# FPGA_Peripherals_Control.net
KiCad netlist of a schematic drawn in Altium Designer
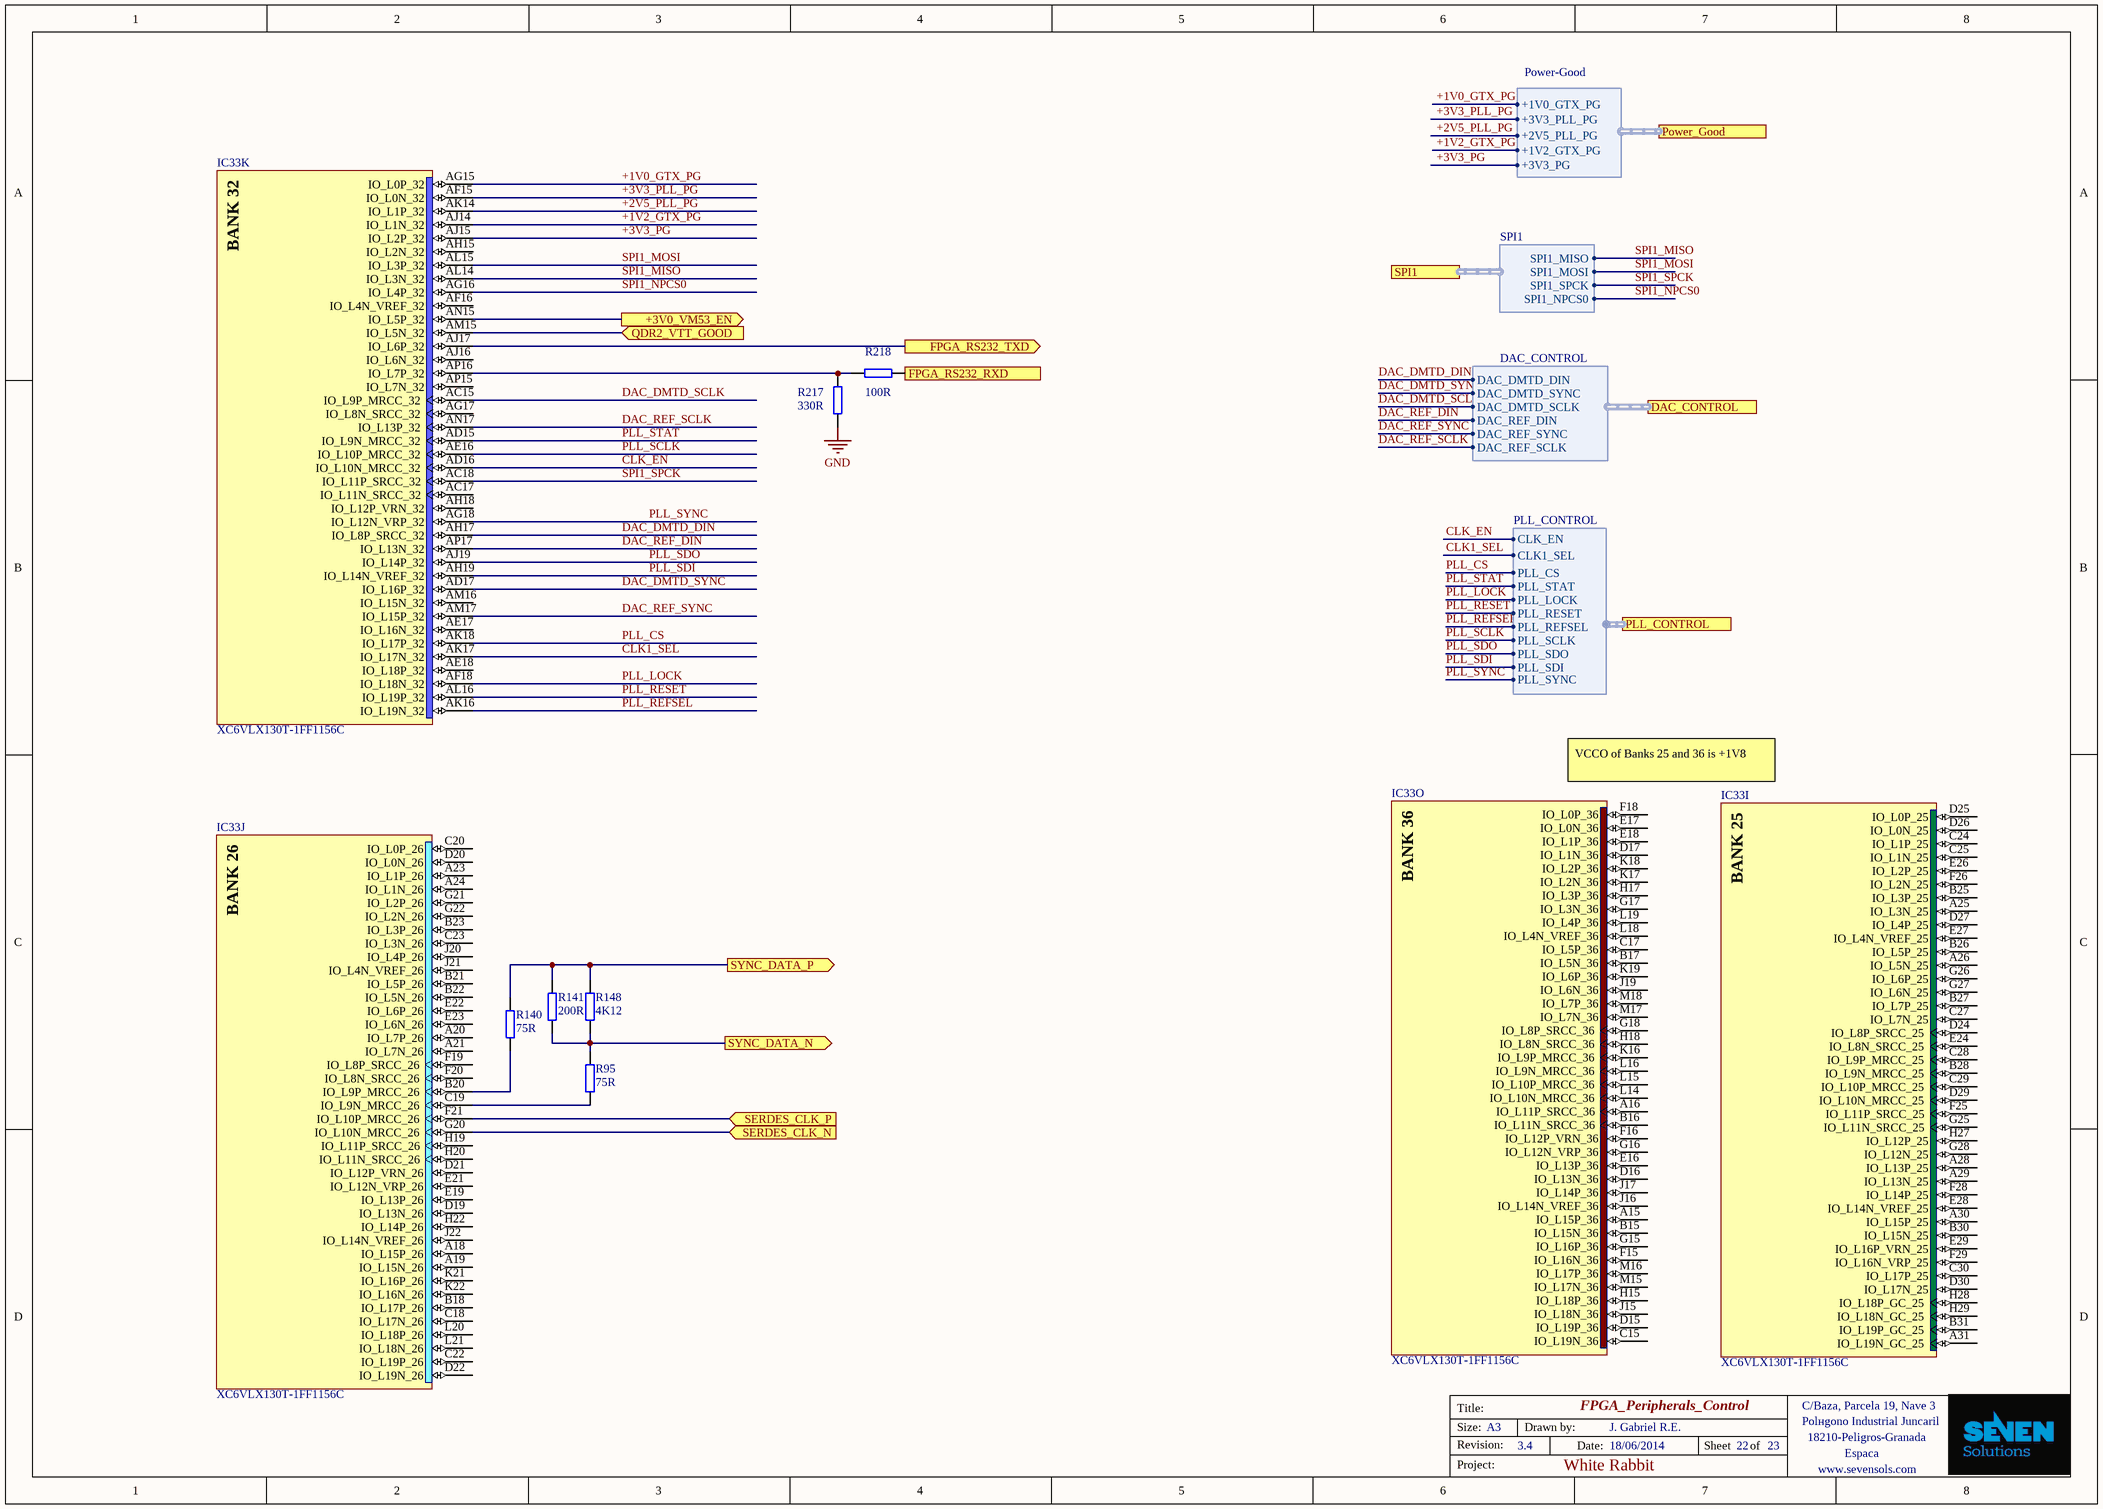
[diagram p0: FPGA_Peripherals_Control.SchDoc]

(export (version "E")
  (design (tool "Eeschema 10.0.6"))
  (components
    (comp (ref "IC33")
      (value "XC6VLX130T-1FF1156C")
      (footprint "FF1156")
      (fields (field (name "PUBLISHER") "Altium Limited"))
      (libsource (lib "Xilinx Virtex-6") (part "XC6VLX130T-1FF1156C"))
    )
    (comp (ref "R95")
      (value "75R")
      (footprint "0402")
      (description "SMD Resistor")
      (fields (field (name "TOLERANCE") "±1%"))
      (libsource (lib "wr_switch") (part "RES_SMD"))
    )
    (comp (ref "R140")
      (value "75R")
      (footprint "0402")
      (description "SMD Resistor")
      (fields (field (name "TOLERANCE") "±1%"))
      (libsource (lib "wr_switch") (part "RES_SMD"))
    )
    (comp (ref "R141")
      (value "200R")
      (footprint "0402")
      (description "SMD Resistor")
      (fields (field (name "TOLERANCE") "±1%"))
      (libsource (lib "wr_switch") (part "RES_SMD"))
    )
    (comp (ref "R148")
      (value "4K12")
      (footprint "0402")
      (description "SMD Resistor")
      (fields (field (name "TOLERANCE") "±1%"))
      (libsource (lib "wr_switch") (part "RES_SMD"))
    )
    (comp (ref "R217")
      (value "330R")
      (footprint "0402")
      (description "SMD Resistor")
      (fields (field (name "TOLERANCE") "±1%"))
      (libsource (lib "wr_switch") (part "RES_SMD"))
    )
    (comp (ref "R218")
      (value "100R")
      (footprint "0402")
      (description "SMD Resistor")
      (fields (field (name "TOLERANCE") "±1%"))
      (libsource (lib "wr_switch") (part "RES_SMD"))
    )
  )
  (nets
    (net (code "5") (name "/+1V0_GTX_PG") (class "Default")
      (node (ref "IC33") (pin "AG15") (pinfunction "IO_L0P_32_AG15") (pintype "bidirectional"))
    )
    (net (code "6") (name "/+1V2_GTX_PG") (class "Default")
      (node (ref "IC33") (pin "AJ14") (pinfunction "IO_L1N_32_AJ14") (pintype "bidirectional"))
    )
    (net (code "7") (name "/+2V5_PLL_PG") (class "Default")
      (node (ref "IC33") (pin "AK14") (pinfunction "IO_L1P_32_AK14") (pintype "bidirectional"))
    )
    (net (code "8") (name "/+3V0_VM53_EN") (class "Default")
      (node (ref "IC33") (pin "AN15") (pinfunction "IO_L5P_32_AN15") (pintype "bidirectional"))
    )
    (net (code "9") (name "/+3V3_PG") (class "Default")
      (node (ref "IC33") (pin "AJ15") (pinfunction "IO_L2P_32_AJ15") (pintype "bidirectional"))
    )
    (net (code "10") (name "/+3V3_PLL_PG") (class "Default")
      (node (ref "IC33") (pin "AF15") (pinfunction "IO_L0N_32_AF15") (pintype "bidirectional"))
    )
    (net (code "11") (name "/CLK1_SEL") (class "Default")
      (node (ref "IC33") (pin "AK17") (pinfunction "IO_L17N_32_AK17") (pintype "bidirectional"))
    )
    (net (code "12") (name "/CLK_EN") (class "Default")
      (node (ref "IC33") (pin "AD16") (pinfunction "IO_L10N_MRCC_32_AD16") (pintype "bidirectional"))
    )
    (net (code "13") (name "/DAC_DMTD_DIN") (class "Default")
      (node (ref "IC33") (pin "AH17") (pinfunction "IO_L8P_SRCC_32_AH17") (pintype "bidirectional"))
    )
    (net (code "14") (name "/DAC_DMTD_SCLK") (class "Default")
      (node (ref "IC33") (pin "AC15") (pinfunction "IO_L9P_MRCC_32_AC15") (pintype "bidirectional"))
    )
    (net (code "15") (name "/DAC_DMTD_SYNC") (class "Default")
      (node (ref "IC33") (pin "AD17") (pinfunction "IO_L16P_32_AD17") (pintype "bidirectional"))
    )
    (net (code "16") (name "/DAC_REF_DIN") (class "Default")
      (node (ref "IC33") (pin "AP17") (pinfunction "IO_L13N_32_AP17") (pintype "bidirectional"))
    )
    (net (code "17") (name "/DAC_REF_SCLK") (class "Default")
      (node (ref "IC33") (pin "AN17") (pinfunction "IO_L13P_32_AN17") (pintype "bidirectional"))
    )
    (net (code "18") (name "/DAC_REF_SYNC") (class "Default")
      (node (ref "IC33") (pin "AM17") (pinfunction "IO_L15P_32_AM17") (pintype "bidirectional"))
    )
    (net (code "19") (name "/FPGA_RS232_RXD") (class "Default")
      (node (ref "R218") (pin "1") (pinfunction "1_1") (pintype "passive"))
    )
    (net (code "20") (name "/FPGA_RS232_TXD") (class "Default")
      (node (ref "IC33") (pin "AJ17") (pinfunction "IO_L6P_32_AJ17") (pintype "bidirectional"))
    )
    (net (code "21") (name "/PLL_CS") (class "Default")
      (node (ref "IC33") (pin "AK18") (pinfunction "IO_L17P_32_AK18") (pintype "bidirectional"))
    )
    (net (code "22") (name "/PLL_LOCK") (class "Default")
      (node (ref "IC33") (pin "AF18") (pinfunction "IO_L18N_32_AF18") (pintype "bidirectional"))
    )
    (net (code "23") (name "/PLL_REFSEL") (class "Default")
      (node (ref "IC33") (pin "AK16") (pinfunction "IO_L19N_32_AK16") (pintype "bidirectional"))
    )
    (net (code "24") (name "/PLL_RESET") (class "Default")
      (node (ref "IC33") (pin "AL16") (pinfunction "IO_L19P_32_AL16") (pintype "bidirectional"))
    )
    (net (code "25") (name "/PLL_SCLK") (class "Default")
      (node (ref "IC33") (pin "AE16") (pinfunction "IO_L10P_MRCC_32_AE16") (pintype "bidirectional"))
    )
    (net (code "26") (name "/PLL_SDI") (class "Default")
      (node (ref "IC33") (pin "AH19") (pinfunction "IO_L14N_VREF_32_AH19") (pintype "bidirectional"))
    )
    (net (code "27") (name "/PLL_SDO") (class "Default")
      (node (ref "IC33") (pin "AJ19") (pinfunction "IO_L14P_32_AJ19") (pintype "bidirectional"))
    )
    (net (code "28") (name "/PLL_STAT") (class "Default")
      (node (ref "IC33") (pin "AD15") (pinfunction "IO_L9N_MRCC_32_AD15") (pintype "bidirectional"))
    )
    (net (code "29") (name "/PLL_SYNC") (class "Default")
      (node (ref "IC33") (pin "AG18") (pinfunction "IO_L12N_VRP_32_AG18") (pintype "bidirectional"))
    )
    (net (code "30") (name "/QDR2_VTT_GOOD") (class "Default")
      (node (ref "IC33") (pin "AM15") (pinfunction "IO_L5N_32_AM15") (pintype "bidirectional"))
    )
    (net (code "31") (name "/SERDES_CLK_N") (class "Default")
      (node (ref "IC33") (pin "G20") (pinfunction "IO_L10N_MRCC_26_G20") (pintype "bidirectional"))
    )
    (net (code "32") (name "/SERDES_CLK_P") (class "Default")
      (node (ref "IC33") (pin "F21") (pinfunction "IO_L10P_MRCC_26_F21") (pintype "bidirectional"))
    )
    (net (code "33") (name "/SPI1_MISO") (class "Default")
      (node (ref "IC33") (pin "AL14") (pinfunction "IO_L3N_32_AL14") (pintype "bidirectional"))
    )
    (net (code "34") (name "/SPI1_MOSI") (class "Default")
      (node (ref "IC33") (pin "AL15") (pinfunction "IO_L3P_32_AL15") (pintype "bidirectional"))
    )
    (net (code "35") (name "/SPI1_NPCS0") (class "Default")
      (node (ref "IC33") (pin "AG16") (pinfunction "IO_L4P_32_AG16") (pintype "bidirectional"))
    )
    (net (code "36") (name "/SPI1_SPCK") (class "Default")
      (node (ref "IC33") (pin "AC18") (pinfunction "IO_L11P_SRCC_32_AC18") (pintype "bidirectional"))
    )
    (net (code "37") (name "/SYNC_DATA_N") (class "Default")
      (node (ref "R141") (pin "2") (pinfunction "2_2") (pintype "passive"))
      (node (ref "R148") (pin "1") (pinfunction "1_1") (pintype "passive"))
      (node (ref "R95") (pin "2") (pinfunction "2_2") (pintype "passive"))
    )
    (net (code "38") (name "/SYNC_DATA_P") (class "Default")
      (node (ref "R140") (pin "2") (pinfunction "2_2") (pintype "passive"))
      (node (ref "R141") (pin "1") (pinfunction "1_1") (pintype "passive"))
      (node (ref "R148") (pin "2") (pinfunction "2_2") (pintype "passive"))
    )
    (net (code "43") (name "GND") (class "Default")
      (node (ref "R217") (pin "1") (pinfunction "1_1") (pintype "passive"))
    )
    (net (code "44") (name "Net-(IC33J-IO_L9N_MRCC_26)") (class "Default")
      (node (ref "IC33") (pin "C19") (pinfunction "IO_L9N_MRCC_26_C19") (pintype "bidirectional"))
      (node (ref "R95") (pin "1") (pinfunction "1_1") (pintype "passive"))
    )
    (net (code "45") (name "Net-(IC33J-IO_L9P_MRCC_26)") (class "Default")
      (node (ref "IC33") (pin "B20") (pinfunction "IO_L9P_MRCC_26_B20") (pintype "bidirectional"))
      (node (ref "R140") (pin "1") (pinfunction "1_1") (pintype "passive"))
    )
    (net (code "46") (name "Net-(IC33K-IO_L7P_32)") (class "Default")
      (node (ref "IC33") (pin "AP16") (pinfunction "IO_L7P_32_AP16") (pintype "bidirectional"))
      (node (ref "R217") (pin "2") (pinfunction "2_2") (pintype "passive"))
      (node (ref "R218") (pin "2") (pinfunction "2_2") (pintype "passive"))
    )
    (net (code "47") (name "unconnected-(IC33I-IO_L0N_25-PadD26)") (class "Default")
      (node (ref "IC33") (pin "D26") (pinfunction "IO_L0N_25_D26") (pintype "bidirectional"))
    )
    (net (code "48") (name "unconnected-(IC33I-IO_L0P_25-PadD25)") (class "Default")
      (node (ref "IC33") (pin "D25") (pinfunction "IO_L0P_25_D25") (pintype "bidirectional"))
    )
    (net (code "49") (name "unconnected-(IC33I-IO_L1N_25-PadC25)") (class "Default")
      (node (ref "IC33") (pin "C25") (pinfunction "IO_L1N_25_C25") (pintype "bidirectional"))
    )
    (net (code "50") (name "unconnected-(IC33I-IO_L1P_25-PadC24)") (class "Default")
      (node (ref "IC33") (pin "C24") (pinfunction "IO_L1P_25_C24") (pintype "bidirectional"))
    )
    (net (code "51") (name "unconnected-(IC33I-IO_L2N_25-PadF26)") (class "Default")
      (node (ref "IC33") (pin "F26") (pinfunction "IO_L2N_25_F26") (pintype "bidirectional"))
    )
    (net (code "52") (name "unconnected-(IC33I-IO_L2P_25-PadE26)") (class "Default")
      (node (ref "IC33") (pin "E26") (pinfunction "IO_L2P_25_E26") (pintype "bidirectional"))
    )
    (net (code "53") (name "unconnected-(IC33I-IO_L3N_25-PadA25)") (class "Default")
      (node (ref "IC33") (pin "A25") (pinfunction "IO_L3N_25_A25") (pintype "bidirectional"))
    )
    (net (code "54") (name "unconnected-(IC33I-IO_L3P_25-PadB25)") (class "Default")
      (node (ref "IC33") (pin "B25") (pinfunction "IO_L3P_25_B25") (pintype "bidirectional"))
    )
    (net (code "55") (name "unconnected-(IC33I-IO_L4N_VREF_25-PadE27)") (class "Default")
      (node (ref "IC33") (pin "E27") (pinfunction "IO_L4N_VREF_25_E27") (pintype "bidirectional"))
    )
    (net (code "56") (name "unconnected-(IC33I-IO_L4P_25-PadD27)") (class "Default")
      (node (ref "IC33") (pin "D27") (pinfunction "IO_L4P_25_D27") (pintype "bidirectional"))
    )
    (net (code "57") (name "unconnected-(IC33I-IO_L5N_25-PadA26)") (class "Default")
      (node (ref "IC33") (pin "A26") (pinfunction "IO_L5N_25_A26") (pintype "bidirectional"))
    )
    (net (code "58") (name "unconnected-(IC33I-IO_L5P_25-PadB26)") (class "Default")
      (node (ref "IC33") (pin "B26") (pinfunction "IO_L5P_25_B26") (pintype "bidirectional"))
    )
    (net (code "59") (name "unconnected-(IC33I-IO_L6N_25-PadG27)") (class "Default")
      (node (ref "IC33") (pin "G27") (pinfunction "IO_L6N_25_G27") (pintype "bidirectional"))
    )
    (net (code "60") (name "unconnected-(IC33I-IO_L6P_25-PadG26)") (class "Default")
      (node (ref "IC33") (pin "G26") (pinfunction "IO_L6P_25_G26") (pintype "bidirectional"))
    )
    (net (code "61") (name "unconnected-(IC33I-IO_L7N_25-PadC27)") (class "Default")
      (node (ref "IC33") (pin "C27") (pinfunction "IO_L7N_25_C27") (pintype "bidirectional"))
    )
    (net (code "62") (name "unconnected-(IC33I-IO_L7P_25-PadB27)") (class "Default")
      (node (ref "IC33") (pin "B27") (pinfunction "IO_L7P_25_B27") (pintype "bidirectional"))
    )
    (net (code "63") (name "unconnected-(IC33I-IO_L8N_SRCC_25-PadE24)") (class "Default")
      (node (ref "IC33") (pin "E24") (pinfunction "IO_L8N_SRCC_25_E24") (pintype "bidirectional"))
    )
    (net (code "64") (name "unconnected-(IC33I-IO_L8P_SRCC_25-PadD24)") (class "Default")
      (node (ref "IC33") (pin "D24") (pinfunction "IO_L8P_SRCC_25_D24") (pintype "bidirectional"))
    )
    (net (code "65") (name "unconnected-(IC33I-IO_L9N_MRCC_25-PadB28)") (class "Default")
      (node (ref "IC33") (pin "B28") (pinfunction "IO_L9N_MRCC_25_B28") (pintype "bidirectional"))
    )
    (net (code "66") (name "unconnected-(IC33I-IO_L9P_MRCC_25-PadC28)") (class "Default")
      (node (ref "IC33") (pin "C28") (pinfunction "IO_L9P_MRCC_25_C28") (pintype "bidirectional"))
    )
    (net (code "67") (name "unconnected-(IC33I-IO_L10N_MRCC_25-PadD29)") (class "Default")
      (node (ref "IC33") (pin "D29") (pinfunction "IO_L10N_MRCC_25_D29") (pintype "bidirectional"))
    )
    (net (code "68") (name "unconnected-(IC33I-IO_L10P_MRCC_25-PadC29)") (class "Default")
      (node (ref "IC33") (pin "C29") (pinfunction "IO_L10P_MRCC_25_C29") (pintype "bidirectional"))
    )
    (net (code "69") (name "unconnected-(IC33I-IO_L11N_SRCC_25-PadG25)") (class "Default")
      (node (ref "IC33") (pin "G25") (pinfunction "IO_L11N_SRCC_25_G25") (pintype "bidirectional"))
    )
    (net (code "70") (name "unconnected-(IC33I-IO_L11P_SRCC_25-PadF25)") (class "Default")
      (node (ref "IC33") (pin "F25") (pinfunction "IO_L11P_SRCC_25_F25") (pintype "bidirectional"))
    )
    (net (code "71") (name "unconnected-(IC33I-IO_L12N_25-PadG28)") (class "Default")
      (node (ref "IC33") (pin "G28") (pinfunction "IO_L12N_25_G28") (pintype "bidirectional"))
    )
    (net (code "72") (name "unconnected-(IC33I-IO_L12P_25-PadH27)") (class "Default")
      (node (ref "IC33") (pin "H27") (pinfunction "IO_L12P_25_H27") (pintype "bidirectional"))
    )
    (net (code "73") (name "unconnected-(IC33I-IO_L13N_25-PadA29)") (class "Default")
      (node (ref "IC33") (pin "A29") (pinfunction "IO_L13N_25_A29") (pintype "bidirectional"))
    )
    (net (code "74") (name "unconnected-(IC33I-IO_L13P_25-PadA28)") (class "Default")
      (node (ref "IC33") (pin "A28") (pinfunction "IO_L13P_25_A28") (pintype "bidirectional"))
    )
    (net (code "75") (name "unconnected-(IC33I-IO_L14N_VREF_25-PadE28)") (class "Default")
      (node (ref "IC33") (pin "E28") (pinfunction "IO_L14N_VREF_25_E28") (pintype "bidirectional"))
    )
    (net (code "76") (name "unconnected-(IC33I-IO_L14P_25-PadF28)") (class "Default")
      (node (ref "IC33") (pin "F28") (pinfunction "IO_L14P_25_F28") (pintype "bidirectional"))
    )
    (net (code "77") (name "unconnected-(IC33I-IO_L15N_25-PadB30)") (class "Default")
      (node (ref "IC33") (pin "B30") (pinfunction "IO_L15N_25_B30") (pintype "bidirectional"))
    )
    (net (code "78") (name "unconnected-(IC33I-IO_L15P_25-PadA30)") (class "Default")
      (node (ref "IC33") (pin "A30") (pinfunction "IO_L15P_25_A30") (pintype "bidirectional"))
    )
    (net (code "79") (name "unconnected-(IC33I-IO_L16N_VRP_25-PadF29)") (class "Default")
      (node (ref "IC33") (pin "F29") (pinfunction "IO_L16N_VRP_25_F29") (pintype "bidirectional"))
    )
    (net (code "80") (name "unconnected-(IC33I-IO_L16P_VRN_25-PadE29)") (class "Default")
      (node (ref "IC33") (pin "E29") (pinfunction "IO_L16P_VRN_25_E29") (pintype "bidirectional"))
    )
    (net (code "81") (name "unconnected-(IC33I-IO_L17N_25-PadD30)") (class "Default")
      (node (ref "IC33") (pin "D30") (pinfunction "IO_L17N_25_D30") (pintype "bidirectional"))
    )
    (net (code "82") (name "unconnected-(IC33I-IO_L17P_25-PadC30)") (class "Default")
      (node (ref "IC33") (pin "C30") (pinfunction "IO_L17P_25_C30") (pintype "bidirectional"))
    )
    (net (code "83") (name "unconnected-(IC33I-IO_L18N_GC_25-PadH29)") (class "Default")
      (node (ref "IC33") (pin "H29") (pinfunction "IO_L18N_GC_25_H29") (pintype "bidirectional"))
    )
    (net (code "84") (name "unconnected-(IC33I-IO_L18P_GC_25-PadH28)") (class "Default")
      (node (ref "IC33") (pin "H28") (pinfunction "IO_L18P_GC_25_H28") (pintype "bidirectional"))
    )
    (net (code "85") (name "unconnected-(IC33I-IO_L19N_GC_25-PadA31)") (class "Default")
      (node (ref "IC33") (pin "A31") (pinfunction "IO_L19N_GC_25_A31") (pintype "bidirectional"))
    )
    (net (code "86") (name "unconnected-(IC33I-IO_L19P_GC_25-PadB31)") (class "Default")
      (node (ref "IC33") (pin "B31") (pinfunction "IO_L19P_GC_25_B31") (pintype "bidirectional"))
    )
    (net (code "87") (name "unconnected-(IC33J-IO_L0N_26-PadD20)") (class "Default")
      (node (ref "IC33") (pin "D20") (pinfunction "IO_L0N_26_D20") (pintype "bidirectional"))
    )
    (net (code "88") (name "unconnected-(IC33J-IO_L0P_26-PadC20)") (class "Default")
      (node (ref "IC33") (pin "C20") (pinfunction "IO_L0P_26_C20") (pintype "bidirectional"))
    )
    (net (code "89") (name "unconnected-(IC33J-IO_L1N_26-PadA24)") (class "Default")
      (node (ref "IC33") (pin "A24") (pinfunction "IO_L1N_26_A24") (pintype "bidirectional"))
    )
    (net (code "90") (name "unconnected-(IC33J-IO_L1P_26-PadA23)") (class "Default")
      (node (ref "IC33") (pin "A23") (pinfunction "IO_L1P_26_A23") (pintype "bidirectional"))
    )
    (net (code "91") (name "unconnected-(IC33J-IO_L2N_26-PadG22)") (class "Default")
      (node (ref "IC33") (pin "G22") (pinfunction "IO_L2N_26_G22") (pintype "bidirectional"))
    )
    (net (code "92") (name "unconnected-(IC33J-IO_L2P_26-PadG21)") (class "Default")
      (node (ref "IC33") (pin "G21") (pinfunction "IO_L2P_26_G21") (pintype "bidirectional"))
    )
    (net (code "93") (name "unconnected-(IC33J-IO_L3N_26-PadC23)") (class "Default")
      (node (ref "IC33") (pin "C23") (pinfunction "IO_L3N_26_C23") (pintype "bidirectional"))
    )
    (net (code "94") (name "unconnected-(IC33J-IO_L3P_26-PadB23)") (class "Default")
      (node (ref "IC33") (pin "B23") (pinfunction "IO_L3P_26_B23") (pintype "bidirectional"))
    )
    (net (code "95") (name "unconnected-(IC33J-IO_L4N_VREF_26-PadJ21)") (class "Default")
      (node (ref "IC33") (pin "J21") (pinfunction "IO_L4N_VREF_26_J21") (pintype "bidirectional"))
    )
    (net (code "96") (name "unconnected-(IC33J-IO_L4P_26-PadJ20)") (class "Default")
      (node (ref "IC33") (pin "J20") (pinfunction "IO_L4P_26_J20") (pintype "bidirectional"))
    )
    (net (code "97") (name "unconnected-(IC33J-IO_L5N_26-PadB22)") (class "Default")
      (node (ref "IC33") (pin "B22") (pinfunction "IO_L5N_26_B22") (pintype "bidirectional"))
    )
    (net (code "98") (name "unconnected-(IC33J-IO_L5P_26-PadB21)") (class "Default")
      (node (ref "IC33") (pin "B21") (pinfunction "IO_L5P_26_B21") (pintype "bidirectional"))
    )
    (net (code "99") (name "unconnected-(IC33J-IO_L6N_26-PadE23)") (class "Default")
      (node (ref "IC33") (pin "E23") (pinfunction "IO_L6N_26_E23") (pintype "bidirectional"))
    )
    (net (code "100") (name "unconnected-(IC33J-IO_L6P_26-PadE22)") (class "Default")
      (node (ref "IC33") (pin "E22") (pinfunction "IO_L6P_26_E22") (pintype "bidirectional"))
    )
    (net (code "101") (name "unconnected-(IC33J-IO_L7N_26-PadA21)") (class "Default")
      (node (ref "IC33") (pin "A21") (pinfunction "IO_L7N_26_A21") (pintype "bidirectional"))
    )
    (net (code "102") (name "unconnected-(IC33J-IO_L7P_26-PadA20)") (class "Default")
      (node (ref "IC33") (pin "A20") (pinfunction "IO_L7P_26_A20") (pintype "bidirectional"))
    )
    (net (code "103") (name "unconnected-(IC33J-IO_L8N_SRCC_26-PadF20)") (class "Default")
      (node (ref "IC33") (pin "F20") (pinfunction "IO_L8N_SRCC_26_F20") (pintype "bidirectional"))
    )
    (net (code "104") (name "unconnected-(IC33J-IO_L8P_SRCC_26-PadF19)") (class "Default")
      (node (ref "IC33") (pin "F19") (pinfunction "IO_L8P_SRCC_26_F19") (pintype "bidirectional"))
    )
    (net (code "105") (name "unconnected-(IC33J-IO_L11N_SRCC_26-PadH20)") (class "Default")
      (node (ref "IC33") (pin "H20") (pinfunction "IO_L11N_SRCC_26_H20") (pintype "bidirectional"))
    )
    (net (code "106") (name "unconnected-(IC33J-IO_L11P_SRCC_26-PadH19)") (class "Default")
      (node (ref "IC33") (pin "H19") (pinfunction "IO_L11P_SRCC_26_H19") (pintype "bidirectional"))
    )
    (net (code "107") (name "unconnected-(IC33J-IO_L12N_VRP_26-PadE21)") (class "Default")
      (node (ref "IC33") (pin "E21") (pinfunction "IO_L12N_VRP_26_E21") (pintype "bidirectional"))
    )
    (net (code "108") (name "unconnected-(IC33J-IO_L12P_VRN_26-PadD21)") (class "Default")
      (node (ref "IC33") (pin "D21") (pinfunction "IO_L12P_VRN_26_D21") (pintype "bidirectional"))
    )
    (net (code "109") (name "unconnected-(IC33J-IO_L13N_26-PadD19)") (class "Default")
      (node (ref "IC33") (pin "D19") (pinfunction "IO_L13N_26_D19") (pintype "bidirectional"))
    )
    (net (code "110") (name "unconnected-(IC33J-IO_L13P_26-PadE19)") (class "Default")
      (node (ref "IC33") (pin "E19") (pinfunction "IO_L13P_26_E19") (pintype "bidirectional"))
    )
    (net (code "111") (name "unconnected-(IC33J-IO_L14N_VREF_26-PadJ22)") (class "Default")
      (node (ref "IC33") (pin "J22") (pinfunction "IO_L14N_VREF_26_J22") (pintype "bidirectional"))
    )
    (net (code "112") (name "unconnected-(IC33J-IO_L14P_26-PadH22)") (class "Default")
      (node (ref "IC33") (pin "H22") (pinfunction "IO_L14P_26_H22") (pintype "bidirectional"))
    )
    (net (code "113") (name "unconnected-(IC33J-IO_L15N_26-PadA19)") (class "Default")
      (node (ref "IC33") (pin "A19") (pinfunction "IO_L15N_26_A19") (pintype "bidirectional"))
    )
    (net (code "114") (name "unconnected-(IC33J-IO_L15P_26-PadA18)") (class "Default")
      (node (ref "IC33") (pin "A18") (pinfunction "IO_L15P_26_A18") (pintype "bidirectional"))
    )
    (net (code "115") (name "unconnected-(IC33J-IO_L16N_26-PadK22)") (class "Default")
      (node (ref "IC33") (pin "K22") (pinfunction "IO_L16N_26_K22") (pintype "bidirectional"))
    )
    (net (code "116") (name "unconnected-(IC33J-IO_L16P_26-PadK21)") (class "Default")
      (node (ref "IC33") (pin "K21") (pinfunction "IO_L16P_26_K21") (pintype "bidirectional"))
    )
    (net (code "117") (name "unconnected-(IC33J-IO_L17N_26-PadC18)") (class "Default")
      (node (ref "IC33") (pin "C18") (pinfunction "IO_L17N_26_C18") (pintype "bidirectional"))
    )
    (net (code "118") (name "unconnected-(IC33J-IO_L17P_26-PadB18)") (class "Default")
      (node (ref "IC33") (pin "B18") (pinfunction "IO_L17P_26_B18") (pintype "bidirectional"))
    )
    (net (code "119") (name "unconnected-(IC33J-IO_L18N_26-PadL21)") (class "Default")
      (node (ref "IC33") (pin "L21") (pinfunction "IO_L18N_26_L21") (pintype "bidirectional"))
    )
    (net (code "120") (name "unconnected-(IC33J-IO_L18P_26-PadL20)") (class "Default")
      (node (ref "IC33") (pin "L20") (pinfunction "IO_L18P_26_L20") (pintype "bidirectional"))
    )
    (net (code "121") (name "unconnected-(IC33J-IO_L19N_26-PadD22)") (class "Default")
      (node (ref "IC33") (pin "D22") (pinfunction "IO_L19N_26_D22") (pintype "bidirectional"))
    )
    (net (code "122") (name "unconnected-(IC33J-IO_L19P_26-PadC22)") (class "Default")
      (node (ref "IC33") (pin "C22") (pinfunction "IO_L19P_26_C22") (pintype "bidirectional"))
    )
    (net (code "123") (name "unconnected-(IC33K-IO_L2N_32-PadAH15)") (class "Default")
      (node (ref "IC33") (pin "AH15") (pinfunction "IO_L2N_32_AH15") (pintype "bidirectional"))
    )
    (net (code "124") (name "unconnected-(IC33K-IO_L4N_VREF_32-PadAF16)") (class "Default")
      (node (ref "IC33") (pin "AF16") (pinfunction "IO_L4N_VREF_32_AF16") (pintype "bidirectional"))
    )
    (net (code "125") (name "unconnected-(IC33K-IO_L6N_32-PadAJ16)") (class "Default")
      (node (ref "IC33") (pin "AJ16") (pinfunction "IO_L6N_32_AJ16") (pintype "bidirectional"))
    )
    (net (code "126") (name "unconnected-(IC33K-IO_L7N_32-PadAP15)") (class "Default")
      (node (ref "IC33") (pin "AP15") (pinfunction "IO_L7N_32_AP15") (pintype "bidirectional"))
    )
    (net (code "127") (name "unconnected-(IC33K-IO_L8N_SRCC_32-PadAG17)") (class "Default")
      (node (ref "IC33") (pin "AG17") (pinfunction "IO_L8N_SRCC_32_AG17") (pintype "bidirectional"))
    )
    (net (code "128") (name "unconnected-(IC33K-IO_L11N_SRCC_32-PadAC17)") (class "Default")
      (node (ref "IC33") (pin "AC17") (pinfunction "IO_L11N_SRCC_32_AC17") (pintype "bidirectional"))
    )
    (net (code "129") (name "unconnected-(IC33K-IO_L12P_VRN_32-PadAH18)") (class "Default")
      (node (ref "IC33") (pin "AH18") (pinfunction "IO_L12P_VRN_32_AH18") (pintype "bidirectional"))
    )
    (net (code "130") (name "unconnected-(IC33K-IO_L15N_32-PadAM16)") (class "Default")
      (node (ref "IC33") (pin "AM16") (pinfunction "IO_L15N_32_AM16") (pintype "bidirectional"))
    )
    (net (code "131") (name "unconnected-(IC33K-IO_L16N_32-PadAE17)") (class "Default")
      (node (ref "IC33") (pin "AE17") (pinfunction "IO_L16N_32_AE17") (pintype "bidirectional"))
    )
    (net (code "132") (name "unconnected-(IC33K-IO_L18P_32-PadAE18)") (class "Default")
      (node (ref "IC33") (pin "AE18") (pinfunction "IO_L18P_32_AE18") (pintype "bidirectional"))
    )
    (net (code "133") (name "unconnected-(IC33O-IO_L0N_36-PadE17)") (class "Default")
      (node (ref "IC33") (pin "E17") (pinfunction "IO_L0N_36_E17") (pintype "bidirectional"))
    )
    (net (code "134") (name "unconnected-(IC33O-IO_L0P_36-PadF18)") (class "Default")
      (node (ref "IC33") (pin "F18") (pinfunction "IO_L0P_36_F18") (pintype "bidirectional"))
    )
    (net (code "135") (name "unconnected-(IC33O-IO_L1N_36-PadD17)") (class "Default")
      (node (ref "IC33") (pin "D17") (pinfunction "IO_L1N_36_D17") (pintype "bidirectional"))
    )
    (net (code "136") (name "unconnected-(IC33O-IO_L1P_36-PadE18)") (class "Default")
      (node (ref "IC33") (pin "E18") (pinfunction "IO_L1P_36_E18") (pintype "bidirectional"))
    )
    (net (code "137") (name "unconnected-(IC33O-IO_L2N_36-PadK17)") (class "Default")
      (node (ref "IC33") (pin "K17") (pinfunction "IO_L2N_36_K17") (pintype "bidirectional"))
    )
    (net (code "138") (name "unconnected-(IC33O-IO_L2P_36-PadK18)") (class "Default")
      (node (ref "IC33") (pin "K18") (pinfunction "IO_L2P_36_K18") (pintype "bidirectional"))
    )
    (net (code "139") (name "unconnected-(IC33O-IO_L3N_36-PadG17)") (class "Default")
      (node (ref "IC33") (pin "G17") (pinfunction "IO_L3N_36_G17") (pintype "bidirectional"))
    )
    (net (code "140") (name "unconnected-(IC33O-IO_L3P_36-PadH17)") (class "Default")
      (node (ref "IC33") (pin "H17") (pinfunction "IO_L3P_36_H17") (pintype "bidirectional"))
    )
    (net (code "141") (name "unconnected-(IC33O-IO_L4N_VREF_36-PadL18)") (class "Default")
      (node (ref "IC33") (pin "L18") (pinfunction "IO_L4N_VREF_36_L18") (pintype "bidirectional"))
    )
    (net (code "142") (name "unconnected-(IC33O-IO_L4P_36-PadL19)") (class "Default")
      (node (ref "IC33") (pin "L19") (pinfunction "IO_L4P_36_L19") (pintype "bidirectional"))
    )
    (net (code "143") (name "unconnected-(IC33O-IO_L5N_36-PadB17)") (class "Default")
      (node (ref "IC33") (pin "B17") (pinfunction "IO_L5N_36_B17") (pintype "bidirectional"))
    )
    (net (code "144") (name "unconnected-(IC33O-IO_L5P_36-PadC17)") (class "Default")
      (node (ref "IC33") (pin "C17") (pinfunction "IO_L5P_36_C17") (pintype "bidirectional"))
    )
    (net (code "145") (name "unconnected-(IC33O-IO_L6N_36-PadJ19)") (class "Default")
      (node (ref "IC33") (pin "J19") (pinfunction "IO_L6N_36_J19") (pintype "bidirectional"))
    )
    (net (code "146") (name "unconnected-(IC33O-IO_L6P_36-PadK19)") (class "Default")
      (node (ref "IC33") (pin "K19") (pinfunction "IO_L6P_36_K19") (pintype "bidirectional"))
    )
    (net (code "147") (name "unconnected-(IC33O-IO_L7N_36-PadM17)") (class "Default")
      (node (ref "IC33") (pin "M17") (pinfunction "IO_L7N_36_M17") (pintype "bidirectional"))
    )
    (net (code "148") (name "unconnected-(IC33O-IO_L7P_36-PadM18)") (class "Default")
      (node (ref "IC33") (pin "M18") (pinfunction "IO_L7P_36_M18") (pintype "bidirectional"))
    )
    (net (code "149") (name "unconnected-(IC33O-IO_L8N_SRCC_36-PadH18)") (class "Default")
      (node (ref "IC33") (pin "H18") (pinfunction "IO_L8N_SRCC_36_H18") (pintype "bidirectional"))
    )
    (net (code "150") (name "unconnected-(IC33O-IO_L8P_SRCC_36-PadG18)") (class "Default")
      (node (ref "IC33") (pin "G18") (pinfunction "IO_L8P_SRCC_36_G18") (pintype "bidirectional"))
    )
    (net (code "151") (name "unconnected-(IC33O-IO_L9N_MRCC_36-PadL16)") (class "Default")
      (node (ref "IC33") (pin "L16") (pinfunction "IO_L9N_MRCC_36_L16") (pintype "bidirectional"))
    )
    (net (code "152") (name "unconnected-(IC33O-IO_L9P_MRCC_36-PadK16)") (class "Default")
      (node (ref "IC33") (pin "K16") (pinfunction "IO_L9P_MRCC_36_K16") (pintype "bidirectional"))
    )
    (net (code "153") (name "unconnected-(IC33O-IO_L10N_MRCC_36-PadL14)") (class "Default")
      (node (ref "IC33") (pin "L14") (pinfunction "IO_L10N_MRCC_36_L14") (pintype "bidirectional"))
    )
    (net (code "154") (name "unconnected-(IC33O-IO_L10P_MRCC_36-PadL15)") (class "Default")
      (node (ref "IC33") (pin "L15") (pinfunction "IO_L10P_MRCC_36_L15") (pintype "bidirectional"))
    )
    (net (code "155") (name "unconnected-(IC33O-IO_L11N_SRCC_36-PadB16)") (class "Default")
      (node (ref "IC33") (pin "B16") (pinfunction "IO_L11N_SRCC_36_B16") (pintype "bidirectional"))
    )
    (net (code "156") (name "unconnected-(IC33O-IO_L11P_SRCC_36-PadA16)") (class "Default")
      (node (ref "IC33") (pin "A16") (pinfunction "IO_L11P_SRCC_36_A16") (pintype "bidirectional"))
    )
    (net (code "157") (name "unconnected-(IC33O-IO_L12N_VRP_36-PadG16)") (class "Default")
      (node (ref "IC33") (pin "G16") (pinfunction "IO_L12N_VRP_36_G16") (pintype "bidirectional"))
    )
    (net (code "158") (name "unconnected-(IC33O-IO_L12P_VRN_36-PadF16)") (class "Default")
      (node (ref "IC33") (pin "F16") (pinfunction "IO_L12P_VRN_36_F16") (pintype "bidirectional"))
    )
    (net (code "159") (name "unconnected-(IC33O-IO_L13N_36-PadD16)") (class "Default")
      (node (ref "IC33") (pin "D16") (pinfunction "IO_L13N_36_D16") (pintype "bidirectional"))
    )
    (net (code "160") (name "unconnected-(IC33O-IO_L13P_36-PadE16)") (class "Default")
      (node (ref "IC33") (pin "E16") (pinfunction "IO_L13P_36_E16") (pintype "bidirectional"))
    )
    (net (code "161") (name "unconnected-(IC33O-IO_L14N_VREF_36-PadJ16)") (class "Default")
      (node (ref "IC33") (pin "J16") (pinfunction "IO_L14N_VREF_36_J16") (pintype "bidirectional"))
    )
    (net (code "162") (name "unconnected-(IC33O-IO_L14P_36-PadJ17)") (class "Default")
      (node (ref "IC33") (pin "J17") (pinfunction "IO_L14P_36_J17") (pintype "bidirectional"))
    )
    (net (code "163") (name "unconnected-(IC33O-IO_L15N_36-PadB15)") (class "Default")
      (node (ref "IC33") (pin "B15") (pinfunction "IO_L15N_36_B15") (pintype "bidirectional"))
    )
    (net (code "164") (name "unconnected-(IC33O-IO_L15P_36-PadA15)") (class "Default")
      (node (ref "IC33") (pin "A15") (pinfunction "IO_L15P_36_A15") (pintype "bidirectional"))
    )
    (net (code "165") (name "unconnected-(IC33O-IO_L16N_36-PadF15)") (class "Default")
      (node (ref "IC33") (pin "F15") (pinfunction "IO_L16N_36_F15") (pintype "bidirectional"))
    )
    (net (code "166") (name "unconnected-(IC33O-IO_L16P_36-PadG15)") (class "Default")
      (node (ref "IC33") (pin "G15") (pinfunction "IO_L16P_36_G15") (pintype "bidirectional"))
    )
    (net (code "167") (name "unconnected-(IC33O-IO_L17N_36-PadM15)") (class "Default")
      (node (ref "IC33") (pin "M15") (pinfunction "IO_L17N_36_M15") (pintype "bidirectional"))
    )
    (net (code "168") (name "unconnected-(IC33O-IO_L17P_36-PadM16)") (class "Default")
      (node (ref "IC33") (pin "M16") (pinfunction "IO_L17P_36_M16") (pintype "bidirectional"))
    )
    (net (code "169") (name "unconnected-(IC33O-IO_L18N_36-PadJ15)") (class "Default")
      (node (ref "IC33") (pin "J15") (pinfunction "IO_L18N_36_J15") (pintype "bidirectional"))
    )
    (net (code "170") (name "unconnected-(IC33O-IO_L18P_36-PadH15)") (class "Default")
      (node (ref "IC33") (pin "H15") (pinfunction "IO_L18P_36_H15") (pintype "bidirectional"))
    )
    (net (code "171") (name "unconnected-(IC33O-IO_L19N_36-PadC15)") (class "Default")
      (node (ref "IC33") (pin "C15") (pinfunction "IO_L19N_36_C15") (pintype "bidirectional"))
    )
    (net (code "172") (name "unconnected-(IC33O-IO_L19P_36-PadD15)") (class "Default")
      (node (ref "IC33") (pin "D15") (pinfunction "IO_L19P_36_D15") (pintype "bidirectional"))
    )
  )
)
